# Circuit_photorecepteur.net
KiCad netlist of a schematic drawn in Altium Designer
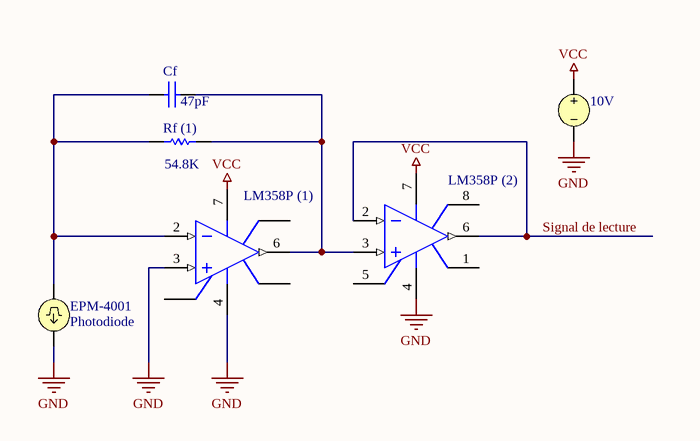
[diagram p0: Circuit photorecepteur.SchDoc]

(export (version "E")
  (design (tool "Eeschema 10.0.6"))
  (components
    (comp (ref "Cf")
      (value "47pF")
      (footprint "RAD-0.3")
      (description "Capacitor")
      (fields (field (name "Comment") "Cap") (field (name "PUBLISHER") "Altium Limited"))
      (libsource (lib "Miscellaneous Devices") (part "Cap"))
    )
    (comp (ref "EPM-4001")
      (value "Photodiode")
      (description "Pulse Current Source")
      (fields (field (name "PUBLISHER") "Altium Limited"))
      (libsource (lib "Simulation Sources") (part "IPULSE"))
    )
    (comp (ref "LM358P (1)")
      (value "Op Amp")
      (footprint "H-08A")
      (description "FET Operational Amplifier")
      (fields (field (name "PUBLISHER") "Altium Limited"))
      (libsource (lib "Miscellaneous Devices") (part "Op Amp"))
    )
    (comp (ref "LM358P (2)")
      (value "Op Amp")
      (footprint "H-08A")
      (description "FET Operational Amplifier")
      (fields (field (name "PUBLISHER") "Altium Limited"))
      (libsource (lib "Miscellaneous Devices") (part "Op Amp"))
    )
    (comp (ref "Rf (1)")
      (value "54.8K")
      (footprint "AXIAL-0.3")
      (description "Resistor")
      (fields (field (name "Comment") "Res1") (field (name "PUBLISHER") "Altium Limited"))
      (libsource (lib "Miscellaneous Devices") (part "Res1"))
    )
    (comp (ref "V1")
      (value "10V")
      (description "Voltage Source")
      (fields (field (name "Comment") "VSRC") (field (name "PUBLISHER") "Altium Limited"))
      (libsource (lib "Simulation Sources") (part "VSRC"))
    )
  )
  (nets
    (net (code "1") (name "/Signal de lecture") (class "Default")
      (node (ref "LM358P (2)") (pin "2") (pinfunction "IN-_2") (pintype "input"))
      (node (ref "LM358P (2)") (pin "6") (pinfunction "OUT_6") (pintype "output"))
    )
    (net (code "2") (name "GND") (class "Default")
      (node (ref "EPM-4001") (pin "2") (pinfunction "2_2") (pintype "passive"))
      (node (ref "LM358P (1)") (pin "3") (pinfunction "IN+_3") (pintype "input"))
      (node (ref "LM358P (1)") (pin "4") (pinfunction "V-_4") (pintype "power_in"))
      (node (ref "LM358P (2)") (pin "4") (pinfunction "V-_4") (pintype "power_in"))
      (node (ref "V1") (pin "2") (pinfunction "2_2") (pintype "passive"))
    )
    (net (code "3") (name "Net-(LM358P (1)-IN-)") (class "Default")
      (node (ref "Cf") (pin "1") (pinfunction "1_1") (pintype "passive"))
      (node (ref "EPM-4001") (pin "1") (pinfunction "1_1") (pintype "passive"))
      (node (ref "LM358P (1)") (pin "2") (pinfunction "IN-_2") (pintype "input"))
      (node (ref "Rf (1)") (pin "1") (pinfunction "1_1") (pintype "passive"))
    )
    (net (code "4") (name "Net-(LM358P (1)-OUT)") (class "Default")
      (node (ref "Cf") (pin "2") (pinfunction "2_2") (pintype "passive"))
      (node (ref "LM358P (1)") (pin "6") (pinfunction "OUT_6") (pintype "output"))
      (node (ref "LM358P (2)") (pin "3") (pinfunction "IN+_3") (pintype "input"))
      (node (ref "Rf (1)") (pin "2") (pinfunction "2_2") (pintype "passive"))
    )
    (net (code "5") (name "VCC") (class "Default")
      (node (ref "LM358P (1)") (pin "7") (pinfunction "V+_7") (pintype "power_in"))
      (node (ref "LM358P (2)") (pin "7") (pinfunction "V+_7") (pintype "power_in"))
      (node (ref "V1") (pin "1") (pinfunction "1_1") (pintype "passive"))
    )
    (net (code "6") (name "unconnected-(LM358P (1)-OS_NUL-Pad1)") (class "Default")
      (node (ref "LM358P (1)") (pin "1") (pinfunction "OS_NUL_1") (pintype "passive"))
    )
    (net (code "7") (name "unconnected-(LM358P (1)-OS_NUL-Pad5)") (class "Default")
      (node (ref "LM358P (1)") (pin "5") (pinfunction "OS_NUL_5") (pintype "passive"))
    )
    (net (code "8") (name "unconnected-(LM358P (1)-TAB-Pad8)") (class "Default")
      (node (ref "LM358P (1)") (pin "8") (pinfunction "TAB_8") (pintype "passive"))
    )
    (net (code "9") (name "unconnected-(LM358P (2)-OS_NUL-Pad1)") (class "Default")
      (node (ref "LM358P (2)") (pin "1") (pinfunction "OS_NUL_1") (pintype "passive"))
    )
    (net (code "10") (name "unconnected-(LM358P (2)-OS_NUL-Pad5)") (class "Default")
      (node (ref "LM358P (2)") (pin "5") (pinfunction "OS_NUL_5") (pintype "passive"))
    )
    (net (code "11") (name "unconnected-(LM358P (2)-TAB-Pad8)") (class "Default")
      (node (ref "LM358P (2)") (pin "8") (pinfunction "TAB_8") (pintype "passive"))
    )
  )
)
